# Pluvion_2_-_vPG.net
KiCad netlist of a schematic drawn in EAGLE
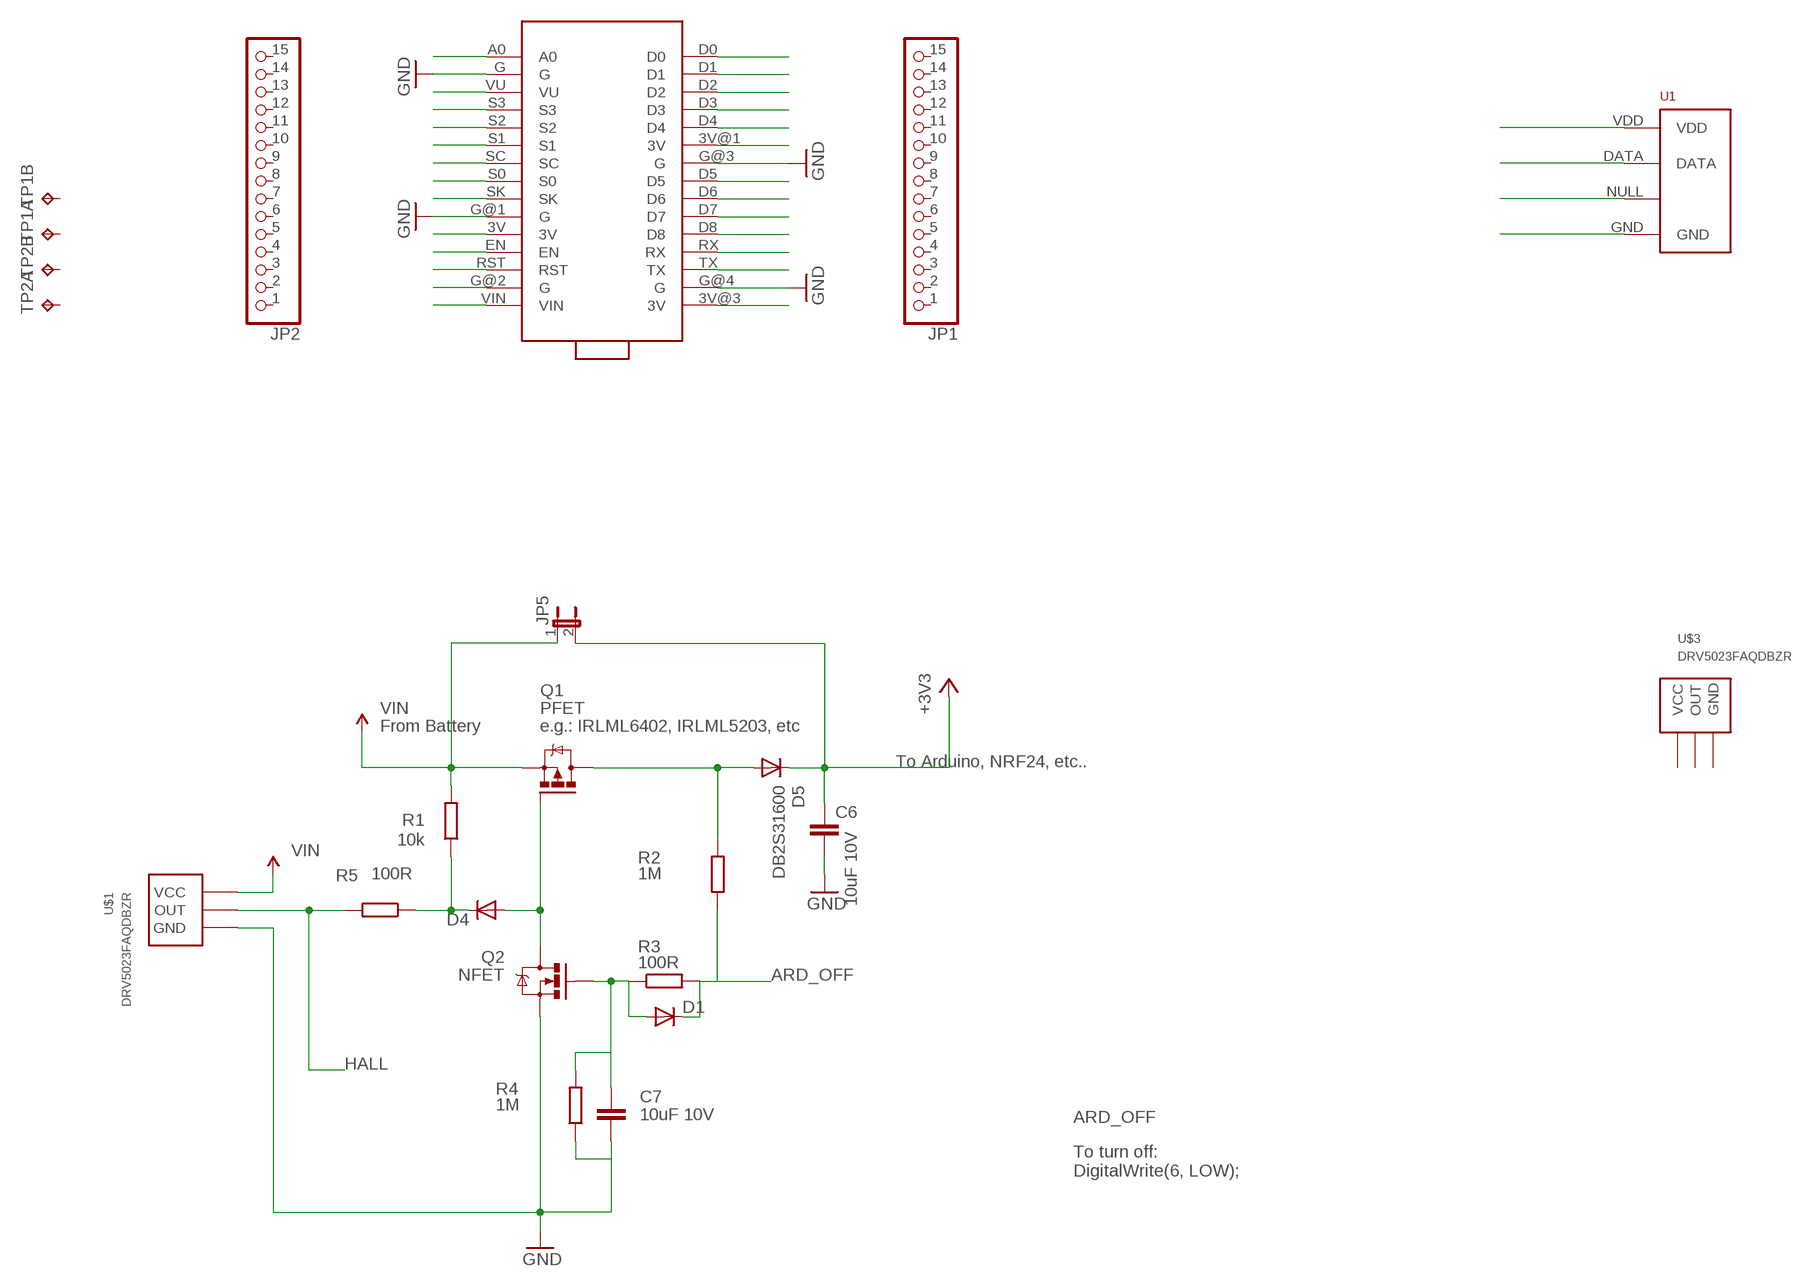
[diagram p0: schematic, sheet 1]

(export (version "E")
  (design (tool "Eeschema 10.0.6"))
  (components
    (comp (ref "C6")
      (value "10uF 10V")
      (footprint "eagle-import:C0805")
      (libsource (lib "eagle-import") (part "C-EUC0805"))
    )
    (comp (ref "C7")
      (value "10uF 10V")
      (footprint "eagle-import:C0805")
      (libsource (lib "eagle-import") (part "C-EUC0805"))
    )
    (comp (ref "D1")
      (value "DIODESMB")
      (footprint "eagle-import:SMB-DIODE")
      (libsource (lib "eagle-import") (part "DIODESMB"))
    )
    (comp (ref "D4")
      (value "DIODESMB")
      (footprint "eagle-import:SMB-DIODE")
      (libsource (lib "eagle-import") (part "DIODESMB"))
    )
    (comp (ref "D5")
      (value "DB2S31600")
      (footprint "eagle-import:SMB-DIODE")
      (libsource (lib "eagle-import") (part "DIODESMB"))
    )
    (comp (ref "JP1")
      (value "PINHD-1X15")
      (footprint "eagle-import:1X15")
      (libsource (lib "eagle-import") (part "PINHD-1X15"))
    )
    (comp (ref "JP2")
      (value "PINHD-1X15")
      (footprint "eagle-import:1X15")
      (libsource (lib "eagle-import") (part "PINHD-1X15"))
    )
    (comp (ref "JP5")
      (value "JUMPER-2PTH")
      (footprint "eagle-import:1X02")
      (libsource (lib "eagle-import") (part "JUMPER-2PTH"))
    )
    (comp (ref "Q1")
      (value "PFET")
      (footprint "eagle-import:MICRO3")
      (libsource (lib "eagle-import") (part "IRLML5203"))
    )
    (comp (ref "Q2")
      (value "NFET")
      (footprint "eagle-import:SOT23")
      (libsource (lib "eagle-import") (part "MOSFET-NCHANNELBSS123LT1G"))
    )
    (comp (ref "R1")
      (value "10k")
      (footprint "eagle-import:R0805")
      (libsource (lib "eagle-import") (part "R-EU_R0805"))
    )
    (comp (ref "R2")
      (value "1M")
      (footprint "eagle-import:R0805")
      (libsource (lib "eagle-import") (part "R-EU_R0805"))
    )
    (comp (ref "R3")
      (value "100R")
      (footprint "eagle-import:R0805")
      (libsource (lib "eagle-import") (part "R-EU_R0805"))
    )
    (comp (ref "R4")
      (value "1M")
      (footprint "eagle-import:R0805")
      (libsource (lib "eagle-import") (part "R-EU_R0805"))
    )
    (comp (ref "R5")
      (value "100R")
      (footprint "eagle-import:R0805")
      (libsource (lib "eagle-import") (part "R-EU_R0805"))
    )
    (comp (ref "TP1")
      (value "TP2P2-38-17")
      (footprint "eagle-import:P2-38-17")
      (libsource (lib "eagle-import") (part "TP2P2-38-17"))
    )
    (comp (ref "TP2")
      (value "TP2P2-38-17")
      (footprint "eagle-import:P2-38-17")
      (libsource (lib "eagle-import") (part "TP2P2-38-17"))
    )
    (comp (ref "U$1")
      (value "DRV5023FAQDBZR")
      (footprint "eagle-import:SOT23")
      (libsource (lib "eagle-import") (part "DRV5023FAQDBZR"))
    )
    (comp (ref "U$2")
      (value "NODE-LOLIN-ESP8266")
      (footprint "eagle-import:NODE-LOLIN-ESP8266")
      (libsource (lib "eagle-import") (part "NODE-LOLIN-ESP8266"))
    )
    (comp (ref "U$3")
      (value "DRV5023FAQDBZR")
      (footprint "eagle-import:SOT23")
      (libsource (lib "eagle-import") (part "DRV5023FAQDBZR"))
    )
    (comp (ref "U1")
      (value "RHT03_DHT-22_AM2302RA")
      (footprint "eagle-import:RHT03_DHT-22_RA")
      (libsource (lib "eagle-import") (part "RHT03_DHT-22_AM2302RA"))
    )
  )
  (nets
    (net (code "1") (name "+3V3") (class "Default")
      (node (ref "C6") (pin "1") (pinfunction "1_1") (pintype "passive"))
      (node (ref "D5") (pin "C") (pinfunction "C_C") (pintype "passive"))
      (node (ref "JP5") (pin "2") (pinfunction "2_2") (pintype "passive"))
    )
    (net (code "2") (name "ARD_OFF") (class "Default")
      (node (ref "D1") (pin "C") (pinfunction "C_C") (pintype "passive"))
      (node (ref "R2") (pin "1") (pinfunction "1_1") (pintype "passive"))
      (node (ref "R3") (pin "2") (pinfunction "2_2") (pintype "passive"))
    )
    (net (code "3") (name "GND") (class "Default")
      (node (ref "C6") (pin "2") (pinfunction "2_2") (pintype "passive"))
      (node (ref "C7") (pin "2") (pinfunction "2_2") (pintype "passive"))
      (node (ref "Q2") (pin "2") (pinfunction "S_2") (pintype "passive"))
      (node (ref "R4") (pin "1") (pinfunction "1_1") (pintype "passive"))
      (node (ref "U$1") (pin "3") (pinfunction "GND_3") (pintype "bidirectional"))
      (node (ref "U$2") (pin "G") (pinfunction "G_G") (pintype "bidirectional"))
      (node (ref "U$2") (pin "G@1") (pinfunction "G_G@1") (pintype "bidirectional"))
      (node (ref "U$2") (pin "G@3") (pinfunction "G_G@3") (pintype "bidirectional"))
      (node (ref "U$2") (pin "G@4") (pinfunction "G_G@4") (pintype "bidirectional"))
    )
    (net (code "4") (name "HALL") (class "Default")
      (node (ref "R5") (pin "2") (pinfunction "2_2") (pintype "passive"))
      (node (ref "U$1") (pin "2") (pinfunction "OUT_2") (pintype "bidirectional"))
    )
    (net (code "5") (name "Net-(D4-PadC)") (class "Default")
      (node (ref "D4") (pin "C") (pinfunction "C_C") (pintype "passive"))
      (node (ref "R1") (pin "1") (pinfunction "1_1") (pintype "passive"))
      (node (ref "R5") (pin "1") (pinfunction "1_1") (pintype "passive"))
    )
    (net (code "6") (name "Net-(Q1-D)") (class "Default")
      (node (ref "D5") (pin "A") (pinfunction "A_A") (pintype "passive"))
      (node (ref "Q1") (pin "3") (pinfunction "D_3") (pintype "passive"))
      (node (ref "R2") (pin "2") (pinfunction "2_2") (pintype "passive"))
    )
    (net (code "7") (name "Net-(Q1-G)") (class "Default")
      (node (ref "D4") (pin "A") (pinfunction "A_A") (pintype "passive"))
      (node (ref "Q1") (pin "1") (pinfunction "G_1") (pintype "passive"))
      (node (ref "Q2") (pin "3") (pinfunction "D_3") (pintype "passive"))
    )
    (net (code "8") (name "Net-(Q2-G)") (class "Default")
      (node (ref "C7") (pin "1") (pinfunction "1_1") (pintype "passive"))
      (node (ref "D1") (pin "A") (pinfunction "A_A") (pintype "passive"))
      (node (ref "Q2") (pin "1") (pinfunction "G_1") (pintype "passive"))
      (node (ref "R3") (pin "1") (pinfunction "1_1") (pintype "passive"))
      (node (ref "R4") (pin "2") (pinfunction "2_2") (pintype "passive"))
    )
    (net (code "9") (name "VIN") (class "Default")
      (node (ref "JP5") (pin "1") (pinfunction "1_1") (pintype "passive"))
      (node (ref "Q1") (pin "2") (pinfunction "S_2") (pintype "passive"))
      (node (ref "R1") (pin "2") (pinfunction "2_2") (pintype "passive"))
      (node (ref "U$1") (pin "1") (pinfunction "VCC_1") (pintype "bidirectional"))
    )
    (net (code "10") (name "unconnected-(JP1-Pad1)") (class "Default")
      (node (ref "JP1") (pin "1") (pinfunction "1_1") (pintype "passive"))
    )
    (net (code "11") (name "unconnected-(JP1-Pad2)") (class "Default")
      (node (ref "JP1") (pin "2") (pinfunction "2_2") (pintype "passive"))
    )
    (net (code "12") (name "unconnected-(JP1-Pad3)") (class "Default")
      (node (ref "JP1") (pin "3") (pinfunction "3_3") (pintype "passive"))
    )
    (net (code "13") (name "unconnected-(JP1-Pad4)") (class "Default")
      (node (ref "JP1") (pin "4") (pinfunction "4_4") (pintype "passive"))
    )
    (net (code "14") (name "unconnected-(JP1-Pad5)") (class "Default")
      (node (ref "JP1") (pin "5") (pinfunction "5_5") (pintype "passive"))
    )
    (net (code "15") (name "unconnected-(JP1-Pad6)") (class "Default")
      (node (ref "JP1") (pin "6") (pinfunction "6_6") (pintype "passive"))
    )
    (net (code "16") (name "unconnected-(JP1-Pad7)") (class "Default")
      (node (ref "JP1") (pin "7") (pinfunction "7_7") (pintype "passive"))
    )
    (net (code "17") (name "unconnected-(JP1-Pad8)") (class "Default")
      (node (ref "JP1") (pin "8") (pinfunction "8_8") (pintype "passive"))
    )
    (net (code "18") (name "unconnected-(JP1-Pad9)") (class "Default")
      (node (ref "JP1") (pin "9") (pinfunction "9_9") (pintype "passive"))
    )
    (net (code "19") (name "unconnected-(JP1-Pad10)") (class "Default")
      (node (ref "JP1") (pin "10") (pinfunction "10_10") (pintype "passive"))
    )
    (net (code "20") (name "unconnected-(JP1-Pad11)") (class "Default")
      (node (ref "JP1") (pin "11") (pinfunction "11_11") (pintype "passive"))
    )
    (net (code "21") (name "unconnected-(JP1-Pad12)") (class "Default")
      (node (ref "JP1") (pin "12") (pinfunction "12_12") (pintype "passive"))
    )
    (net (code "22") (name "unconnected-(JP1-Pad13)") (class "Default")
      (node (ref "JP1") (pin "13") (pinfunction "13_13") (pintype "passive"))
    )
    (net (code "23") (name "unconnected-(JP1-Pad14)") (class "Default")
      (node (ref "JP1") (pin "14") (pinfunction "14_14") (pintype "passive"))
    )
    (net (code "24") (name "unconnected-(JP1-Pad15)") (class "Default")
      (node (ref "JP1") (pin "15") (pinfunction "15_15") (pintype "passive"))
    )
    (net (code "25") (name "unconnected-(JP2-Pad1)") (class "Default")
      (node (ref "JP2") (pin "1") (pinfunction "1_1") (pintype "passive"))
    )
    (net (code "26") (name "unconnected-(JP2-Pad2)") (class "Default")
      (node (ref "JP2") (pin "2") (pinfunction "2_2") (pintype "passive"))
    )
    (net (code "27") (name "unconnected-(JP2-Pad3)") (class "Default")
      (node (ref "JP2") (pin "3") (pinfunction "3_3") (pintype "passive"))
    )
    (net (code "28") (name "unconnected-(JP2-Pad4)") (class "Default")
      (node (ref "JP2") (pin "4") (pinfunction "4_4") (pintype "passive"))
    )
    (net (code "29") (name "unconnected-(JP2-Pad5)") (class "Default")
      (node (ref "JP2") (pin "5") (pinfunction "5_5") (pintype "passive"))
    )
    (net (code "30") (name "unconnected-(JP2-Pad6)") (class "Default")
      (node (ref "JP2") (pin "6") (pinfunction "6_6") (pintype "passive"))
    )
    (net (code "31") (name "unconnected-(JP2-Pad7)") (class "Default")
      (node (ref "JP2") (pin "7") (pinfunction "7_7") (pintype "passive"))
    )
    (net (code "32") (name "unconnected-(JP2-Pad8)") (class "Default")
      (node (ref "JP2") (pin "8") (pinfunction "8_8") (pintype "passive"))
    )
    (net (code "33") (name "unconnected-(JP2-Pad9)") (class "Default")
      (node (ref "JP2") (pin "9") (pinfunction "9_9") (pintype "passive"))
    )
    (net (code "34") (name "unconnected-(JP2-Pad10)") (class "Default")
      (node (ref "JP2") (pin "10") (pinfunction "10_10") (pintype "passive"))
    )
    (net (code "35") (name "unconnected-(JP2-Pad11)") (class "Default")
      (node (ref "JP2") (pin "11") (pinfunction "11_11") (pintype "passive"))
    )
    (net (code "36") (name "unconnected-(JP2-Pad12)") (class "Default")
      (node (ref "JP2") (pin "12") (pinfunction "12_12") (pintype "passive"))
    )
    (net (code "37") (name "unconnected-(JP2-Pad13)") (class "Default")
      (node (ref "JP2") (pin "13") (pinfunction "13_13") (pintype "passive"))
    )
    (net (code "38") (name "unconnected-(JP2-Pad14)") (class "Default")
      (node (ref "JP2") (pin "14") (pinfunction "14_14") (pintype "passive"))
    )
    (net (code "39") (name "unconnected-(JP2-Pad15)") (class "Default")
      (node (ref "JP2") (pin "15") (pinfunction "15_15") (pintype "passive"))
    )
    (net (code "40") (name "unconnected-(TP1A-TP-PadTP-1)") (class "Default")
      (node (ref "TP1") (pin "TP-1") (pinfunction "TP_TP-1") (pintype "input"))
    )
    (net (code "41") (name "unconnected-(TP1B-TP-PadTP-2)") (class "Default")
      (node (ref "TP1") (pin "TP-2") (pinfunction "TP_TP-2") (pintype "input"))
    )
    (net (code "42") (name "unconnected-(TP2A-TP-PadTP-1)") (class "Default")
      (node (ref "TP2") (pin "TP-1") (pinfunction "TP_TP-1") (pintype "input"))
    )
    (net (code "43") (name "unconnected-(TP2B-TP-PadTP-2)") (class "Default")
      (node (ref "TP2") (pin "TP-2") (pinfunction "TP_TP-2") (pintype "input"))
    )
    (net (code "44") (name "unconnected-(U$2-3V-Pad3V@1)") (class "Default")
      (node (ref "U$2") (pin "3V@1") (pinfunction "3V_3V@1") (pintype "bidirectional"))
    )
    (net (code "45") (name "unconnected-(U$2-3V-Pad3V@3)") (class "Default")
      (node (ref "U$2") (pin "3V@3") (pinfunction "3V_3V@3") (pintype "bidirectional"))
    )
    (net (code "46") (name "unconnected-(U$2-G-PadG@2)") (class "Default")
      (node (ref "U$2") (pin "G@2") (pinfunction "G_G@2") (pintype "bidirectional"))
    )
    (net (code "47") (name "unconnected-(U$2-Pad3V)") (class "Default")
      (node (ref "U$2") (pin "3V") (pinfunction "3V_3V") (pintype "bidirectional"))
    )
    (net (code "48") (name "unconnected-(U$2-PadA0)") (class "Default")
      (node (ref "U$2") (pin "A0") (pinfunction "A0_A0") (pintype "bidirectional"))
    )
    (net (code "49") (name "unconnected-(U$2-PadD0)") (class "Default")
      (node (ref "U$2") (pin "D0") (pinfunction "D0_D0") (pintype "bidirectional"))
    )
    (net (code "50") (name "unconnected-(U$2-PadD1)") (class "Default")
      (node (ref "U$2") (pin "D1") (pinfunction "D1_D1") (pintype "bidirectional"))
    )
    (net (code "51") (name "unconnected-(U$2-PadD2)") (class "Default")
      (node (ref "U$2") (pin "D2") (pinfunction "D2_D2") (pintype "bidirectional"))
    )
    (net (code "52") (name "unconnected-(U$2-PadD3)") (class "Default")
      (node (ref "U$2") (pin "D3") (pinfunction "D3_D3") (pintype "bidirectional"))
    )
    (net (code "53") (name "unconnected-(U$2-PadD4)") (class "Default")
      (node (ref "U$2") (pin "D4") (pinfunction "D4_D4") (pintype "bidirectional"))
    )
    (net (code "54") (name "unconnected-(U$2-PadD5)") (class "Default")
      (node (ref "U$2") (pin "D5") (pinfunction "D5_D5") (pintype "bidirectional"))
    )
    (net (code "55") (name "unconnected-(U$2-PadD6)") (class "Default")
      (node (ref "U$2") (pin "D6") (pinfunction "D6_D6") (pintype "bidirectional"))
    )
    (net (code "56") (name "unconnected-(U$2-PadD7)") (class "Default")
      (node (ref "U$2") (pin "D7") (pinfunction "D7_D7") (pintype "bidirectional"))
    )
    (net (code "57") (name "unconnected-(U$2-PadD8)") (class "Default")
      (node (ref "U$2") (pin "D8") (pinfunction "D8_D8") (pintype "bidirectional"))
    )
    (net (code "58") (name "unconnected-(U$2-PadEN)") (class "Default")
      (node (ref "U$2") (pin "EN") (pinfunction "EN_EN") (pintype "bidirectional"))
    )
    (net (code "59") (name "unconnected-(U$2-PadRST)") (class "Default")
      (node (ref "U$2") (pin "RST") (pinfunction "RST_RST") (pintype "bidirectional"))
    )
    (net (code "60") (name "unconnected-(U$2-PadRX)") (class "Default")
      (node (ref "U$2") (pin "RX") (pinfunction "RX_RX") (pintype "bidirectional"))
    )
    (net (code "61") (name "unconnected-(U$2-PadS0)") (class "Default")
      (node (ref "U$2") (pin "S0") (pinfunction "S0_S0") (pintype "bidirectional"))
    )
    (net (code "62") (name "unconnected-(U$2-PadS1)") (class "Default")
      (node (ref "U$2") (pin "S1") (pinfunction "S1_S1") (pintype "bidirectional"))
    )
    (net (code "63") (name "unconnected-(U$2-PadS2)") (class "Default")
      (node (ref "U$2") (pin "S2") (pinfunction "S2_S2") (pintype "bidirectional"))
    )
    (net (code "64") (name "unconnected-(U$2-PadS3)") (class "Default")
      (node (ref "U$2") (pin "S3") (pinfunction "S3_S3") (pintype "bidirectional"))
    )
    (net (code "65") (name "unconnected-(U$2-PadSC)") (class "Default")
      (node (ref "U$2") (pin "SC") (pinfunction "SC_SC") (pintype "bidirectional"))
    )
    (net (code "66") (name "unconnected-(U$2-PadSK)") (class "Default")
      (node (ref "U$2") (pin "SK") (pinfunction "SK_SK") (pintype "bidirectional"))
    )
    (net (code "67") (name "unconnected-(U$2-PadTX)") (class "Default")
      (node (ref "U$2") (pin "TX") (pinfunction "TX_TX") (pintype "bidirectional"))
    )
    (net (code "68") (name "unconnected-(U$2-PadVIN)") (class "Default")
      (node (ref "U$2") (pin "VIN") (pinfunction "VIN_VIN") (pintype "bidirectional"))
    )
    (net (code "69") (name "unconnected-(U$2-PadVU)") (class "Default")
      (node (ref "U$2") (pin "VU") (pinfunction "VU_VU") (pintype "bidirectional"))
    )
    (net (code "70") (name "unconnected-(U$3-GND-Pad3)") (class "Default")
      (node (ref "U$3") (pin "3") (pinfunction "GND_3") (pintype "bidirectional"))
    )
    (net (code "71") (name "unconnected-(U$3-OUT-Pad2)") (class "Default")
      (node (ref "U$3") (pin "2") (pinfunction "OUT_2") (pintype "bidirectional"))
    )
    (net (code "72") (name "unconnected-(U$3-VCC-Pad1)") (class "Default")
      (node (ref "U$3") (pin "1") (pinfunction "VCC_1") (pintype "bidirectional"))
    )
    (net (code "73") (name "unconnected-(U1-PadDATA)") (class "Default")
      (node (ref "U1") (pin "DATA") (pinfunction "DATA_DATA") (pintype "bidirectional"))
    )
    (net (code "74") (name "unconnected-(U1-PadGND)") (class "Default")
      (node (ref "U1") (pin "GND") (pinfunction "GND_GND") (pintype "power_in"))
    )
    (net (code "75") (name "unconnected-(U1-PadNULL)") (class "Default")
      (node (ref "U1") (pin "NULL") (pinfunction "NULL_NULL") (pintype "no_connect"))
    )
    (net (code "76") (name "unconnected-(U1-PadVDD)") (class "Default")
      (node (ref "U1") (pin "VDD") (pinfunction "VDD_VDD") (pintype "power_in"))
    )
  )
)
